# Interface-bottom.net
KiCad netlist of a schematic drawn in Altium Designer
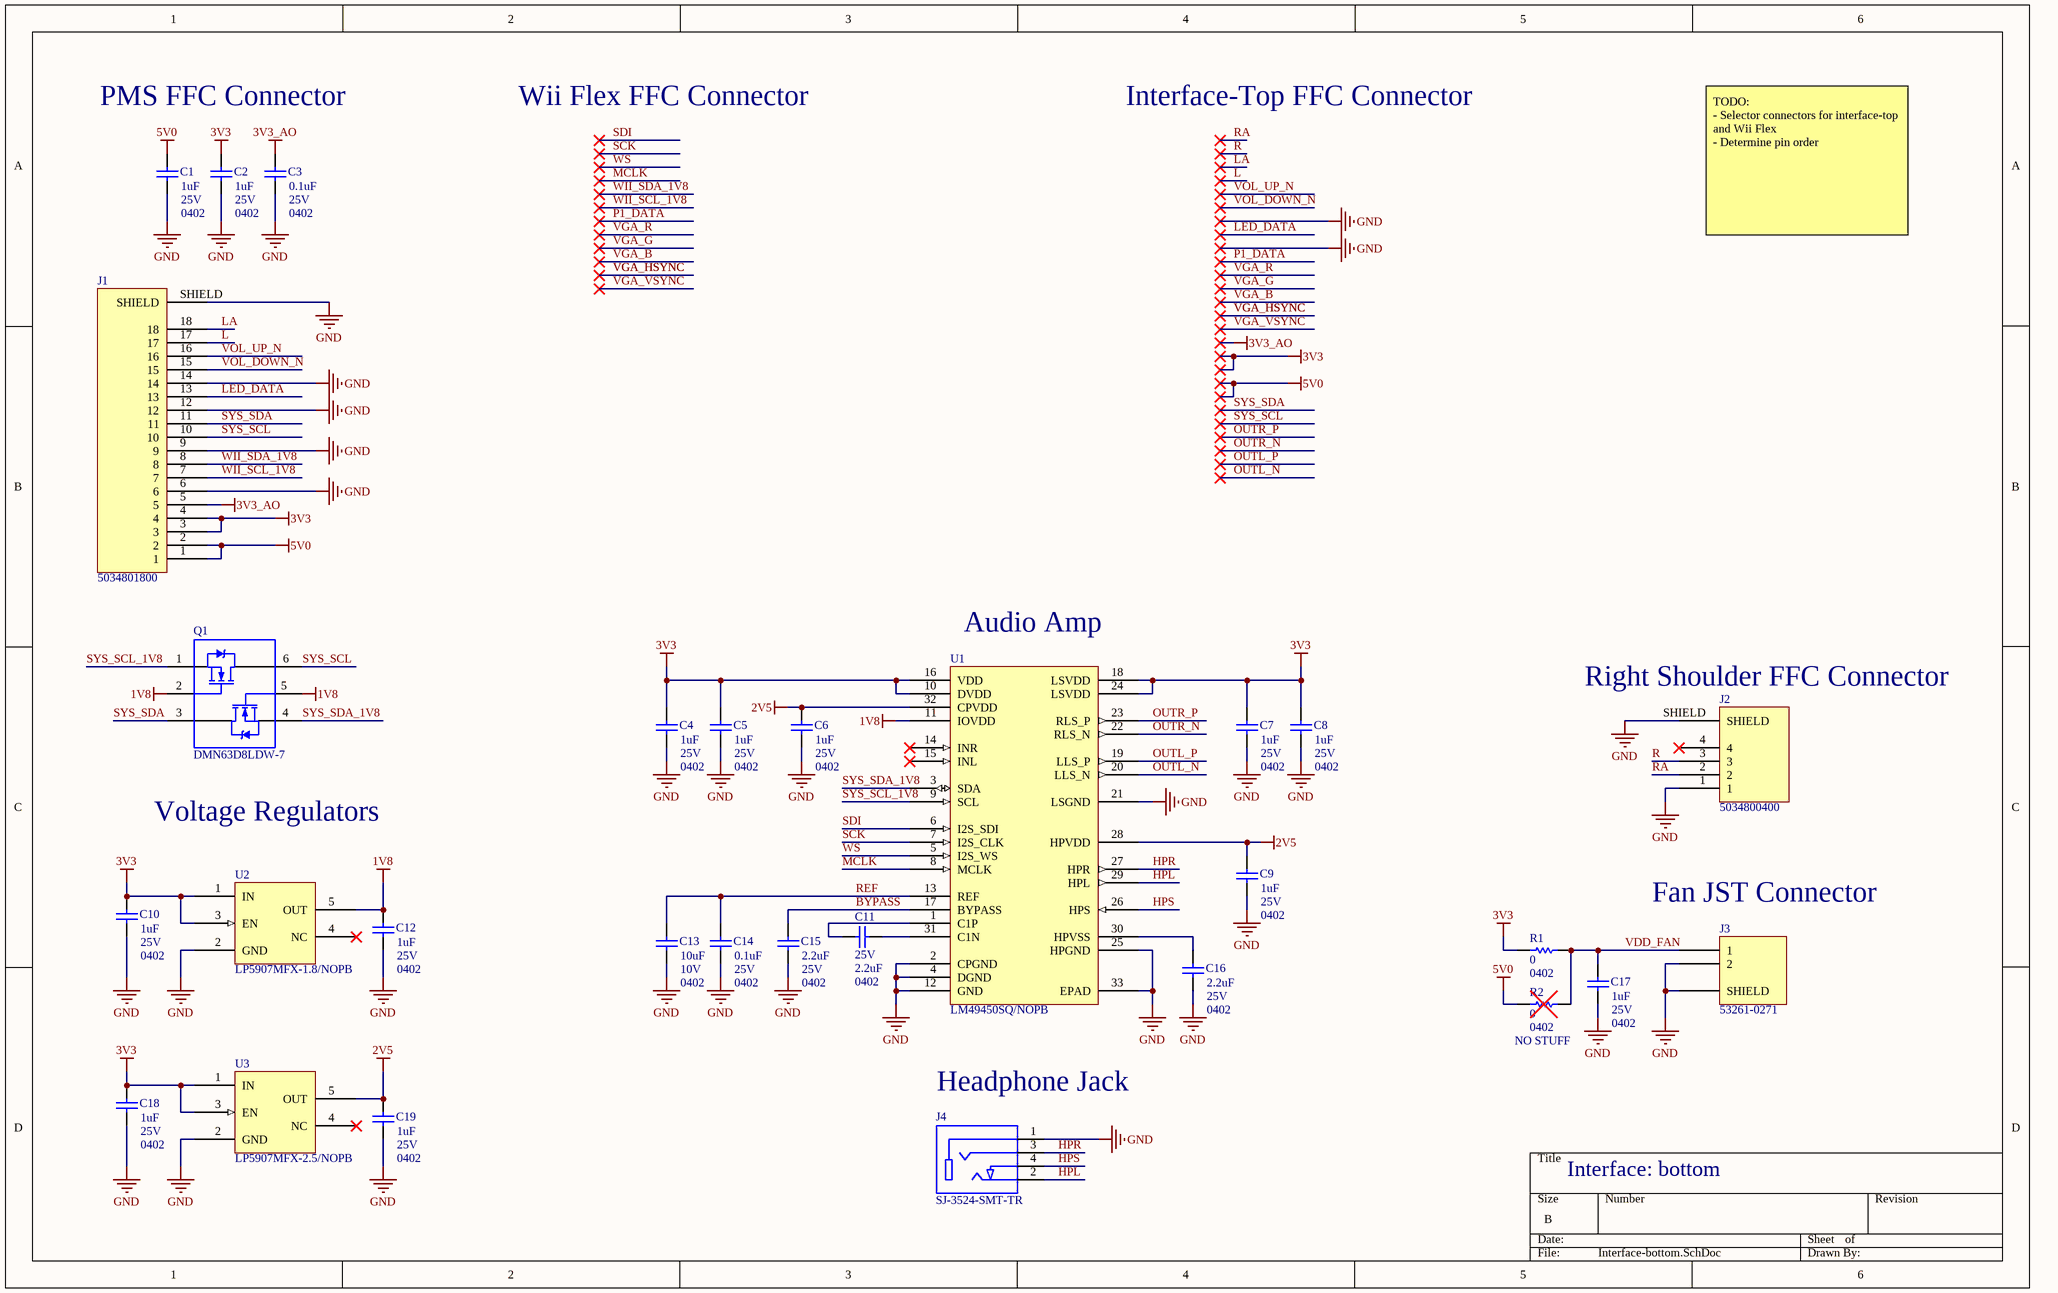
[diagram p0: Interface-bottom.SchDoc]

(export (version "E")
  (design (tool "Eeschema 10.0.6"))
  (components
    (comp (ref "C1")
      (value "1uF")
      (footprint "CAPC1005X06N")
      (description "General purpose capacitor")
      (fields
        (field (name "RATED VOLTAGE") "25V")
        (field (name "PACKAGE") "0402")
        (field (name "Comment") "Capacitor")
      )
      (libsource (lib "Schematic_Generic") (part "Capacitor"))
    )
    (comp (ref "C2")
      (value "1uF")
      (footprint "CAPC1005X06N")
      (description "General purpose capacitor")
      (fields
        (field (name "RATED VOLTAGE") "25V")
        (field (name "PACKAGE") "0402")
        (field (name "Comment") "Capacitor")
      )
      (libsource (lib "Schematic_Generic") (part "Capacitor"))
    )
    (comp (ref "C3")
      (value "0.1uF")
      (footprint "CAPC1005X06N")
      (description "General purpose capacitor")
      (fields
        (field (name "RATED VOLTAGE") "25V")
        (field (name "PACKAGE") "0402")
        (field (name "Comment") "Capacitor")
      )
      (libsource (lib "Schematic_Generic") (part "Capacitor"))
    )
    (comp (ref "C4")
      (value "1uF")
      (footprint "CAPC1005X06N")
      (description "General purpose capacitor")
      (fields
        (field (name "RATED VOLTAGE") "25V")
        (field (name "PACKAGE") "0402")
        (field (name "Comment") "Capacitor")
      )
      (libsource (lib "Schematic_Generic") (part "Capacitor"))
    )
    (comp (ref "C5")
      (value "1uF")
      (footprint "CAPC1005X06N")
      (description "General purpose capacitor")
      (fields
        (field (name "RATED VOLTAGE") "25V")
        (field (name "PACKAGE") "0402")
        (field (name "Comment") "Capacitor")
      )
      (libsource (lib "Schematic_Generic") (part "Capacitor"))
    )
    (comp (ref "C6")
      (value "1uF")
      (footprint "CAPC1005X06N")
      (description "General purpose capacitor")
      (fields
        (field (name "RATED VOLTAGE") "25V")
        (field (name "PACKAGE") "0402")
        (field (name "Comment") "Capacitor")
      )
      (libsource (lib "Schematic_Generic") (part "Capacitor"))
    )
    (comp (ref "C7")
      (value "1uF")
      (footprint "CAPC1005X06N")
      (description "General purpose capacitor")
      (fields
        (field (name "RATED VOLTAGE") "25V")
        (field (name "PACKAGE") "0402")
        (field (name "Comment") "Capacitor")
      )
      (libsource (lib "Schematic_Generic") (part "Capacitor"))
    )
    (comp (ref "C8")
      (value "1uF")
      (footprint "CAPC1005X06N")
      (description "General purpose capacitor")
      (fields
        (field (name "RATED VOLTAGE") "25V")
        (field (name "PACKAGE") "0402")
        (field (name "Comment") "Capacitor")
      )
      (libsource (lib "Schematic_Generic") (part "Capacitor"))
    )
    (comp (ref "C9")
      (value "1uF")
      (footprint "CAPC1005X06N")
      (description "General purpose capacitor")
      (fields
        (field (name "RATED VOLTAGE") "25V")
        (field (name "PACKAGE") "0402")
        (field (name "Comment") "Capacitor")
      )
      (libsource (lib "Schematic_Generic") (part "Capacitor"))
    )
    (comp (ref "C10")
      (value "1uF")
      (footprint "CAPC1005X06N")
      (description "General purpose capacitor")
      (fields
        (field (name "RATED VOLTAGE") "25V")
        (field (name "PACKAGE") "0402")
        (field (name "Comment") "Capacitor")
      )
      (libsource (lib "Schematic_Generic") (part "Capacitor"))
    )
    (comp (ref "C11")
      (value "2.2uF")
      (footprint "CAPC1005X06N")
      (description "General purpose capacitor")
      (fields
        (field (name "RATED VOLTAGE") "25V")
        (field (name "PACKAGE") "0402")
        (field (name "Comment") "Capacitor")
      )
      (libsource (lib "Schematic_Generic") (part "Capacitor"))
    )
    (comp (ref "C12")
      (value "1uF")
      (footprint "CAPC1005X06N")
      (description "General purpose capacitor")
      (fields
        (field (name "RATED VOLTAGE") "25V")
        (field (name "PACKAGE") "0402")
        (field (name "Comment") "Capacitor")
      )
      (libsource (lib "Schematic_Generic") (part "Capacitor"))
    )
    (comp (ref "C13")
      (value "10uF")
      (footprint "CAPC1005X06N")
      (description "General purpose capacitor")
      (fields
        (field (name "RATED VOLTAGE") "10V")
        (field (name "PACKAGE") "0402")
        (field (name "Comment") "Capacitor")
      )
      (libsource (lib "Schematic_Generic") (part "Capacitor"))
    )
    (comp (ref "C14")
      (value "0.1uF")
      (footprint "CAPC1005X06N")
      (description "General purpose capacitor")
      (fields
        (field (name "RATED VOLTAGE") "25V")
        (field (name "PACKAGE") "0402")
        (field (name "Comment") "Capacitor")
      )
      (libsource (lib "Schematic_Generic") (part "Capacitor"))
    )
    (comp (ref "C15")
      (value "2.2uF")
      (footprint "CAPC1005X06N")
      (description "General purpose capacitor")
      (fields
        (field (name "RATED VOLTAGE") "25V")
        (field (name "PACKAGE") "0402")
        (field (name "Comment") "Capacitor")
      )
      (libsource (lib "Schematic_Generic") (part "Capacitor"))
    )
    (comp (ref "C16")
      (value "2.2uF")
      (footprint "CAPC1005X06N")
      (description "General purpose capacitor")
      (fields
        (field (name "RATED VOLTAGE") "25V")
        (field (name "PACKAGE") "0402")
        (field (name "Comment") "Capacitor")
      )
      (libsource (lib "Schematic_Generic") (part "Capacitor"))
    )
    (comp (ref "C17")
      (value "1uF")
      (footprint "CAPC1005X06N")
      (description "General purpose capacitor")
      (fields
        (field (name "RATED VOLTAGE") "25V")
        (field (name "PACKAGE") "0402")
        (field (name "Comment") "Capacitor")
      )
      (libsource (lib "Schematic_Generic") (part "Capacitor"))
    )
    (comp (ref "C18")
      (value "1uF")
      (footprint "CAPC1005X06N")
      (description "General purpose capacitor")
      (fields
        (field (name "RATED VOLTAGE") "25V")
        (field (name "PACKAGE") "0402")
        (field (name "Comment") "Capacitor")
      )
      (libsource (lib "Schematic_Generic") (part "Capacitor"))
    )
    (comp (ref "C19")
      (value "1uF")
      (footprint "CAPC1005X06N")
      (description "General purpose capacitor")
      (fields
        (field (name "RATED VOLTAGE") "25V")
        (field (name "PACKAGE") "0402")
        (field (name "Comment") "Capacitor")
      )
      (libsource (lib "Schematic_Generic") (part "Capacitor"))
    )
    (comp (ref "J1")
      (value "5034801800")
      (footprint "Footprint_Connector:5034801800")
      (description "CONN FFC FPC 18POS 0.50MM R/A")
      (fields (field (name "MANUFACTURER") "Molex"))
      (libsource (lib "Schematic_Connector") (part "5034801800"))
    )
    (comp (ref "J2")
      (value "5034800400")
      (footprint "Footprint_Connector:5034800400")
      (description "CONN FFC FPC 4POS 0.50MM R/A")
      (fields (field (name "MANUFACTURER") "Molex"))
      (libsource (lib "Schematic_Connector") (part "5034800400"))
    )
    (comp (ref "J3")
      (value "53261-0271")
      (footprint "Footprint_Connector:0532610271")
      (description "MOLEX - 53261-0271 - CONNECTOR, HEADER, 2POS, 1ROW, 1.25MM")
      (fields (field (name "MANUFACTURER") "Molex"))
      (libsource (lib "Schematic_Connector") (part "53261-0271"))
    )
    (comp (ref "J4")
      (value "SJ-3524-SMT-TR")
      (footprint "Footprint_Connector:SJ-3524-SMT-TR")
      (description "Conn 3.5MM Audio Jack F 4 POS Solder RA SMD 3 Terminal 1 Port T/R")
      (fields (field (name "MANUFACTURER") "CUI"))
      (libsource (lib "Schematic_Connector") (part "SJ-3524-SMT-TR"))
    )
    (comp (ref "Q1")
      (value "DMN63D8LDW-7")
      (footprint "Footprint_Transistor:SOT65P210X110-6N")
      (description "DIODES INC. - DMN63D8LDW-7 - Dual MOSFET, N Channel, 30 V, 260 mA, 2.8 ohm, SOT-363, Surface Mount")
      (fields (field (name "MANUFACTURER") "Diodes"))
      (libsource (lib "Schematic_Transistor") (part "DMN63D8LDW-7"))
    )
    (comp (ref "R1")
      (value "0")
      (footprint "Footprint_Resistor:RESC1005X04N")
      (description "General purpose resistor")
      (fields (field (name "PACKAGE") "0402") (field (name "Comment") "Resistor"))
      (libsource (lib "Schematic_Generic") (part "Resistor"))
    )
    (comp (ref "R2")
      (value "0")
      (footprint "Footprint_Resistor:RESC1005X04N")
      (description "General purpose resistor")
      (fields
        (field (name "PACKAGE") "0402")
        (field (name "NOTE") "NO STUFF")
        (field (name "Comment") "Resistor")
      )
      (libsource (lib "Schematic_Generic") (part "Resistor"))
    )
    (comp (ref "U1")
      (value "LM49450SQ/NOPB")
      (footprint "Footprint_IC:QFN50P500X500X80_HS-33N")
      (description "IC, AUDIO SUBSYSTEM D 32-LLP")
      (fields (field (name "MANUFACTURER") "TI National Semiconductor"))
      (libsource (lib "Schematic_IC") (part "LM49450SQ/NOPB"))
    )
    (comp (ref "U2")
      (value "LP5907MFX-1.8/NOPB")
      (footprint "Footprint_PMIC:SOT95P280X145-5N")
      (description "IC REG LINEAR 1.8V 250MA SOT23-5")
      (fields (field (name "MANUFACTURER") "Texas Instruments"))
      (libsource (lib "Schematic_PMIC") (part "LP5907MFX-1.8/NOPB"))
    )
    (comp (ref "U3")
      (value "LP5907MFX-2.5/NOPB")
      (footprint "Footprint_PMIC:SOT95P280X145-5N")
      (description "IC REG LINEAR 2.5V 250MA SOT23-5")
      (fields (field (name "MANUFACTURER") "Texas Instruments"))
      (libsource (lib "Schematic_PMIC") (part "LP5907MFX-2.5/NOPB"))
    )
  )
  (nets
    (net (code "1") (name "/BYPASS") (class "Default")
      (node (ref "C15") (pin "2") (pinfunction "2_2") (pintype "passive"))
      (node (ref "U1") (pin "17") (pinfunction "BYPASS_17") (pintype "power_in"))
    )
    (net (code "2") (name "/HPL") (class "Default")
      (node (ref "J4") (pin "2") (pinfunction "2_2") (pintype "passive"))
      (node (ref "U1") (pin "29") (pinfunction "HPL_29") (pintype "output"))
    )
    (net (code "3") (name "/HPR") (class "Default")
      (node (ref "J4") (pin "3") (pinfunction "3_3") (pintype "passive"))
      (node (ref "U1") (pin "27") (pinfunction "HPR_27") (pintype "output"))
    )
    (net (code "4") (name "/HPS") (class "Default")
      (node (ref "J4") (pin "4") (pinfunction "4_4") (pintype "passive"))
      (node (ref "U1") (pin "26") (pinfunction "HPS_26") (pintype "input"))
    )
    (net (code "5") (name "/L") (class "Default")
      (node (ref "J1") (pin "17") (pinfunction "17_17") (pintype "passive"))
    )
    (net (code "6") (name "/LA") (class "Default")
      (node (ref "J1") (pin "18") (pinfunction "18_18") (pintype "passive"))
    )
    (net (code "7") (name "/LED_DATA") (class "Default")
      (node (ref "J1") (pin "13") (pinfunction "13_13") (pintype "passive"))
    )
    (net (code "8") (name "/MCLK") (class "Default")
      (node (ref "U1") (pin "8") (pinfunction "MCLK_8") (pintype "input+no_connect"))
    )
    (net (code "9") (name "/OUTL_N") (class "Default")
      (node (ref "U1") (pin "20") (pinfunction "LLS_N_20") (pintype "output+no_connect"))
    )
    (net (code "10") (name "/OUTL_P") (class "Default")
      (node (ref "U1") (pin "19") (pinfunction "LLS_P_19") (pintype "output+no_connect"))
    )
    (net (code "11") (name "/OUTR_N") (class "Default")
      (node (ref "U1") (pin "22") (pinfunction "RLS_N_22") (pintype "output+no_connect"))
    )
    (net (code "12") (name "/OUTR_P") (class "Default")
      (node (ref "U1") (pin "23") (pinfunction "RLS_P_23") (pintype "output+no_connect"))
    )
    (net (code "14") (name "/R") (class "Default")
      (node (ref "J2") (pin "3") (pinfunction "3_3") (pintype "passive+no_connect"))
    )
    (net (code "15") (name "/RA") (class "Default")
      (node (ref "J2") (pin "2") (pinfunction "2_2") (pintype "passive+no_connect"))
    )
    (net (code "16") (name "/REF") (class "Default")
      (node (ref "C13") (pin "2") (pinfunction "2_2") (pintype "passive"))
      (node (ref "C14") (pin "2") (pinfunction "2_2") (pintype "passive"))
      (node (ref "U1") (pin "13") (pinfunction "REF_13") (pintype "power_in"))
    )
    (net (code "17") (name "/SCK") (class "Default")
      (node (ref "U1") (pin "7") (pinfunction "I2S_CLK_7") (pintype "input+no_connect"))
    )
    (net (code "18") (name "/SDI") (class "Default")
      (node (ref "U1") (pin "6") (pinfunction "I2S_SDI_6") (pintype "input+no_connect"))
    )
    (net (code "19") (name "/SYS_SCL") (class "Default")
      (node (ref "J1") (pin "10") (pinfunction "10_10") (pintype "passive"))
      (node (ref "Q1") (pin "6") (pinfunction "D1_6") (pintype "passive"))
    )
    (net (code "20") (name "/SYS_SCL_1V8") (class "Default")
      (node (ref "Q1") (pin "1") (pinfunction "S1_1") (pintype "passive"))
      (node (ref "U1") (pin "9") (pinfunction "SCL_9") (pintype "input"))
    )
    (net (code "21") (name "/SYS_SDA") (class "Default")
      (node (ref "J1") (pin "11") (pinfunction "11_11") (pintype "passive"))
      (node (ref "Q1") (pin "3") (pinfunction "D2_3") (pintype "passive"))
    )
    (net (code "22") (name "/SYS_SDA_1V8") (class "Default")
      (node (ref "Q1") (pin "4") (pinfunction "S2_4") (pintype "passive"))
      (node (ref "U1") (pin "3") (pinfunction "SDA_3") (pintype "bidirectional"))
    )
    (net (code "23") (name "/VDD_FAN") (class "Default")
      (node (ref "C17") (pin "2") (pinfunction "2_2") (pintype "passive"))
      (node (ref "J3") (pin "1") (pinfunction "1_1") (pintype "passive"))
      (node (ref "R1") (pin "2") (pinfunction "2_2") (pintype "passive"))
      (node (ref "R2") (pin "2") (pinfunction "2_2") (pintype "passive"))
    )
    (net (code "29") (name "/VOL_DOWN_N") (class "Default")
      (node (ref "J1") (pin "15") (pinfunction "15_15") (pintype "passive"))
    )
    (net (code "30") (name "/VOL_UP_N") (class "Default")
      (node (ref "J1") (pin "16") (pinfunction "16_16") (pintype "passive"))
    )
    (net (code "31") (name "/WII_SCL_1V8") (class "Default")
      (node (ref "J1") (pin "7") (pinfunction "7_7") (pintype "passive+no_connect"))
    )
    (net (code "32") (name "/WII_SDA_1V8") (class "Default")
      (node (ref "J1") (pin "8") (pinfunction "8_8") (pintype "passive+no_connect"))
    )
    (net (code "33") (name "/WS") (class "Default")
      (node (ref "U1") (pin "5") (pinfunction "I2S_WS_5") (pintype "input+no_connect"))
    )
    (net (code "34") (name "1V8") (class "Default")
      (node (ref "C12") (pin "2") (pinfunction "2_2") (pintype "passive"))
      (node (ref "Q1") (pin "2") (pinfunction "G1_2") (pintype "passive"))
      (node (ref "Q1") (pin "5") (pinfunction "G2_5") (pintype "passive"))
      (node (ref "U1") (pin "11") (pinfunction "IOVDD_11") (pintype "power_in"))
      (node (ref "U2") (pin "5") (pinfunction "OUT_5") (pintype "power_in"))
    )
    (net (code "35") (name "2V5") (class "Default")
      (node (ref "C19") (pin "2") (pinfunction "2_2") (pintype "passive"))
      (node (ref "C6") (pin "2") (pinfunction "2_2") (pintype "passive"))
      (node (ref "C9") (pin "2") (pinfunction "2_2") (pintype "passive"))
      (node (ref "U1") (pin "28") (pinfunction "HPVDD_28") (pintype "power_in"))
      (node (ref "U1") (pin "32") (pinfunction "CPVDD_32") (pintype "power_in"))
      (node (ref "U3") (pin "5") (pinfunction "OUT_5") (pintype "power_in"))
    )
    (net (code "36") (name "3V3") (class "Default")
      (node (ref "C10") (pin "2") (pinfunction "2_2") (pintype "passive"))
      (node (ref "C18") (pin "2") (pinfunction "2_2") (pintype "passive"))
      (node (ref "C2") (pin "2") (pinfunction "2_2") (pintype "passive"))
      (node (ref "C4") (pin "2") (pinfunction "2_2") (pintype "passive"))
      (node (ref "C5") (pin "2") (pinfunction "2_2") (pintype "passive"))
      (node (ref "C7") (pin "2") (pinfunction "2_2") (pintype "passive"))
      (node (ref "C8") (pin "2") (pinfunction "2_2") (pintype "passive"))
      (node (ref "J1") (pin "3") (pinfunction "3_3") (pintype "passive"))
      (node (ref "J1") (pin "4") (pinfunction "4_4") (pintype "passive"))
      (node (ref "R1") (pin "1") (pinfunction "1_1") (pintype "passive"))
      (node (ref "U1") (pin "10") (pinfunction "DVDD_10") (pintype "power_in"))
      (node (ref "U1") (pin "16") (pinfunction "VDD_16") (pintype "power_in"))
      (node (ref "U1") (pin "18") (pinfunction "LSVDD_18") (pintype "power_in"))
      (node (ref "U1") (pin "24") (pinfunction "LSVDD_24") (pintype "power_in"))
      (node (ref "U2") (pin "1") (pinfunction "IN_1") (pintype "power_in"))
      (node (ref "U2") (pin "3") (pinfunction "EN_3") (pintype "input"))
      (node (ref "U3") (pin "1") (pinfunction "IN_1") (pintype "power_in"))
      (node (ref "U3") (pin "3") (pinfunction "EN_3") (pintype "input"))
    )
    (net (code "37") (name "3V3_AO") (class "Default")
      (node (ref "C3") (pin "2") (pinfunction "2_2") (pintype "passive"))
      (node (ref "J1") (pin "5") (pinfunction "5_5") (pintype "passive"))
    )
    (net (code "38") (name "5V0") (class "Default")
      (node (ref "C1") (pin "2") (pinfunction "2_2") (pintype "passive"))
      (node (ref "J1") (pin "1") (pinfunction "1_1") (pintype "passive"))
      (node (ref "J1") (pin "2") (pinfunction "2_2") (pintype "passive"))
      (node (ref "R2") (pin "1") (pinfunction "1_1") (pintype "passive"))
    )
    (net (code "39") (name "GND") (class "Default")
      (node (ref "C1") (pin "1") (pinfunction "1_1") (pintype "passive"))
      (node (ref "C10") (pin "1") (pinfunction "1_1") (pintype "passive"))
      (node (ref "C12") (pin "1") (pinfunction "1_1") (pintype "passive"))
      (node (ref "C13") (pin "1") (pinfunction "1_1") (pintype "passive"))
      (node (ref "C14") (pin "1") (pinfunction "1_1") (pintype "passive"))
      (node (ref "C15") (pin "1") (pinfunction "1_1") (pintype "passive"))
      (node (ref "C16") (pin "1") (pinfunction "1_1") (pintype "passive"))
      (node (ref "C17") (pin "1") (pinfunction "1_1") (pintype "passive"))
      (node (ref "C18") (pin "1") (pinfunction "1_1") (pintype "passive"))
      (node (ref "C19") (pin "1") (pinfunction "1_1") (pintype "passive"))
      (node (ref "C2") (pin "1") (pinfunction "1_1") (pintype "passive"))
      (node (ref "C3") (pin "1") (pinfunction "1_1") (pintype "passive"))
      (node (ref "C4") (pin "1") (pinfunction "1_1") (pintype "passive"))
      (node (ref "C5") (pin "1") (pinfunction "1_1") (pintype "passive"))
      (node (ref "C6") (pin "1") (pinfunction "1_1") (pintype "passive"))
      (node (ref "C7") (pin "1") (pinfunction "1_1") (pintype "passive"))
      (node (ref "C8") (pin "1") (pinfunction "1_1") (pintype "passive"))
      (node (ref "C9") (pin "1") (pinfunction "1_1") (pintype "passive"))
      (node (ref "J1") (pin "12") (pinfunction "12_12") (pintype "passive"))
      (node (ref "J1") (pin "14") (pinfunction "14_14") (pintype "passive"))
      (node (ref "J1") (pin "6") (pinfunction "6_6") (pintype "passive"))
      (node (ref "J1") (pin "9") (pinfunction "9_9") (pintype "passive"))
      (node (ref "J1") (pin "SHIELD") (pinfunction "SHIELD_SHIELD") (pintype "passive"))
      (node (ref "J2") (pin "1") (pinfunction "1_1") (pintype "passive"))
      (node (ref "J2") (pin "SHIELD") (pinfunction "SHIELD_SHIELD") (pintype "passive"))
      (node (ref "J3") (pin "2") (pinfunction "2_2") (pintype "passive"))
      (node (ref "J3") (pin "SHIELD") (pinfunction "SHIELD_SHIELD") (pintype "passive"))
      (node (ref "J4") (pin "1") (pinfunction "1_1") (pintype "passive"))
      (node (ref "U1") (pin "12") (pinfunction "GND_12") (pintype "power_in"))
      (node (ref "U1") (pin "2") (pinfunction "CPGND_2") (pintype "power_in"))
      (node (ref "U1") (pin "21") (pinfunction "LSGND_21") (pintype "power_in"))
      (node (ref "U1") (pin "25") (pinfunction "HPGND_25") (pintype "power_in"))
      (node (ref "U1") (pin "33") (pinfunction "EPAD_33") (pintype "passive"))
      (node (ref "U1") (pin "4") (pinfunction "DGND_4") (pintype "power_in"))
      (node (ref "U2") (pin "2") (pinfunction "GND_2") (pintype "power_in"))
      (node (ref "U3") (pin "2") (pinfunction "GND_2") (pintype "power_in"))
    )
    (net (code "40") (name "Net-(U1-C1N)") (class "Default")
      (node (ref "C11") (pin "1") (pinfunction "1_1") (pintype "passive"))
      (node (ref "U1") (pin "31") (pinfunction "C1N_31") (pintype "power_in"))
    )
    (net (code "41") (name "Net-(U1-C1P)") (class "Default")
      (node (ref "C11") (pin "2") (pinfunction "2_2") (pintype "passive"))
      (node (ref "U1") (pin "1") (pinfunction "C1P_1") (pintype "power_in"))
    )
    (net (code "42") (name "Net-(U1-HPVSS)") (class "Default")
      (node (ref "C16") (pin "2") (pinfunction "2_2") (pintype "passive"))
      (node (ref "U1") (pin "30") (pinfunction "HPVSS_30") (pintype "power_in"))
    )
    (net (code "43") (name "unconnected-(J2-Pad4)") (class "Default")
      (node (ref "J2") (pin "4") (pinfunction "4_4") (pintype "passive+no_connect"))
    )
    (net (code "44") (name "unconnected-(U1-INL-Pad15)") (class "Default")
      (node (ref "U1") (pin "15") (pinfunction "INL_15") (pintype "input+no_connect"))
    )
    (net (code "45") (name "unconnected-(U1-INR-Pad14)") (class "Default")
      (node (ref "U1") (pin "14") (pinfunction "INR_14") (pintype "input+no_connect"))
    )
    (net (code "46") (name "unconnected-(U2-NC-Pad4)") (class "Default")
      (node (ref "U2") (pin "4") (pinfunction "NC_4") (pintype "passive+no_connect"))
    )
    (net (code "47") (name "unconnected-(U3-NC-Pad4)") (class "Default")
      (node (ref "U3") (pin "4") (pinfunction "NC_4") (pintype "passive+no_connect"))
    )
  )
)
